# AltiumSTM32_Schematic.net
KiCad netlist of a schematic drawn in Altium Designer
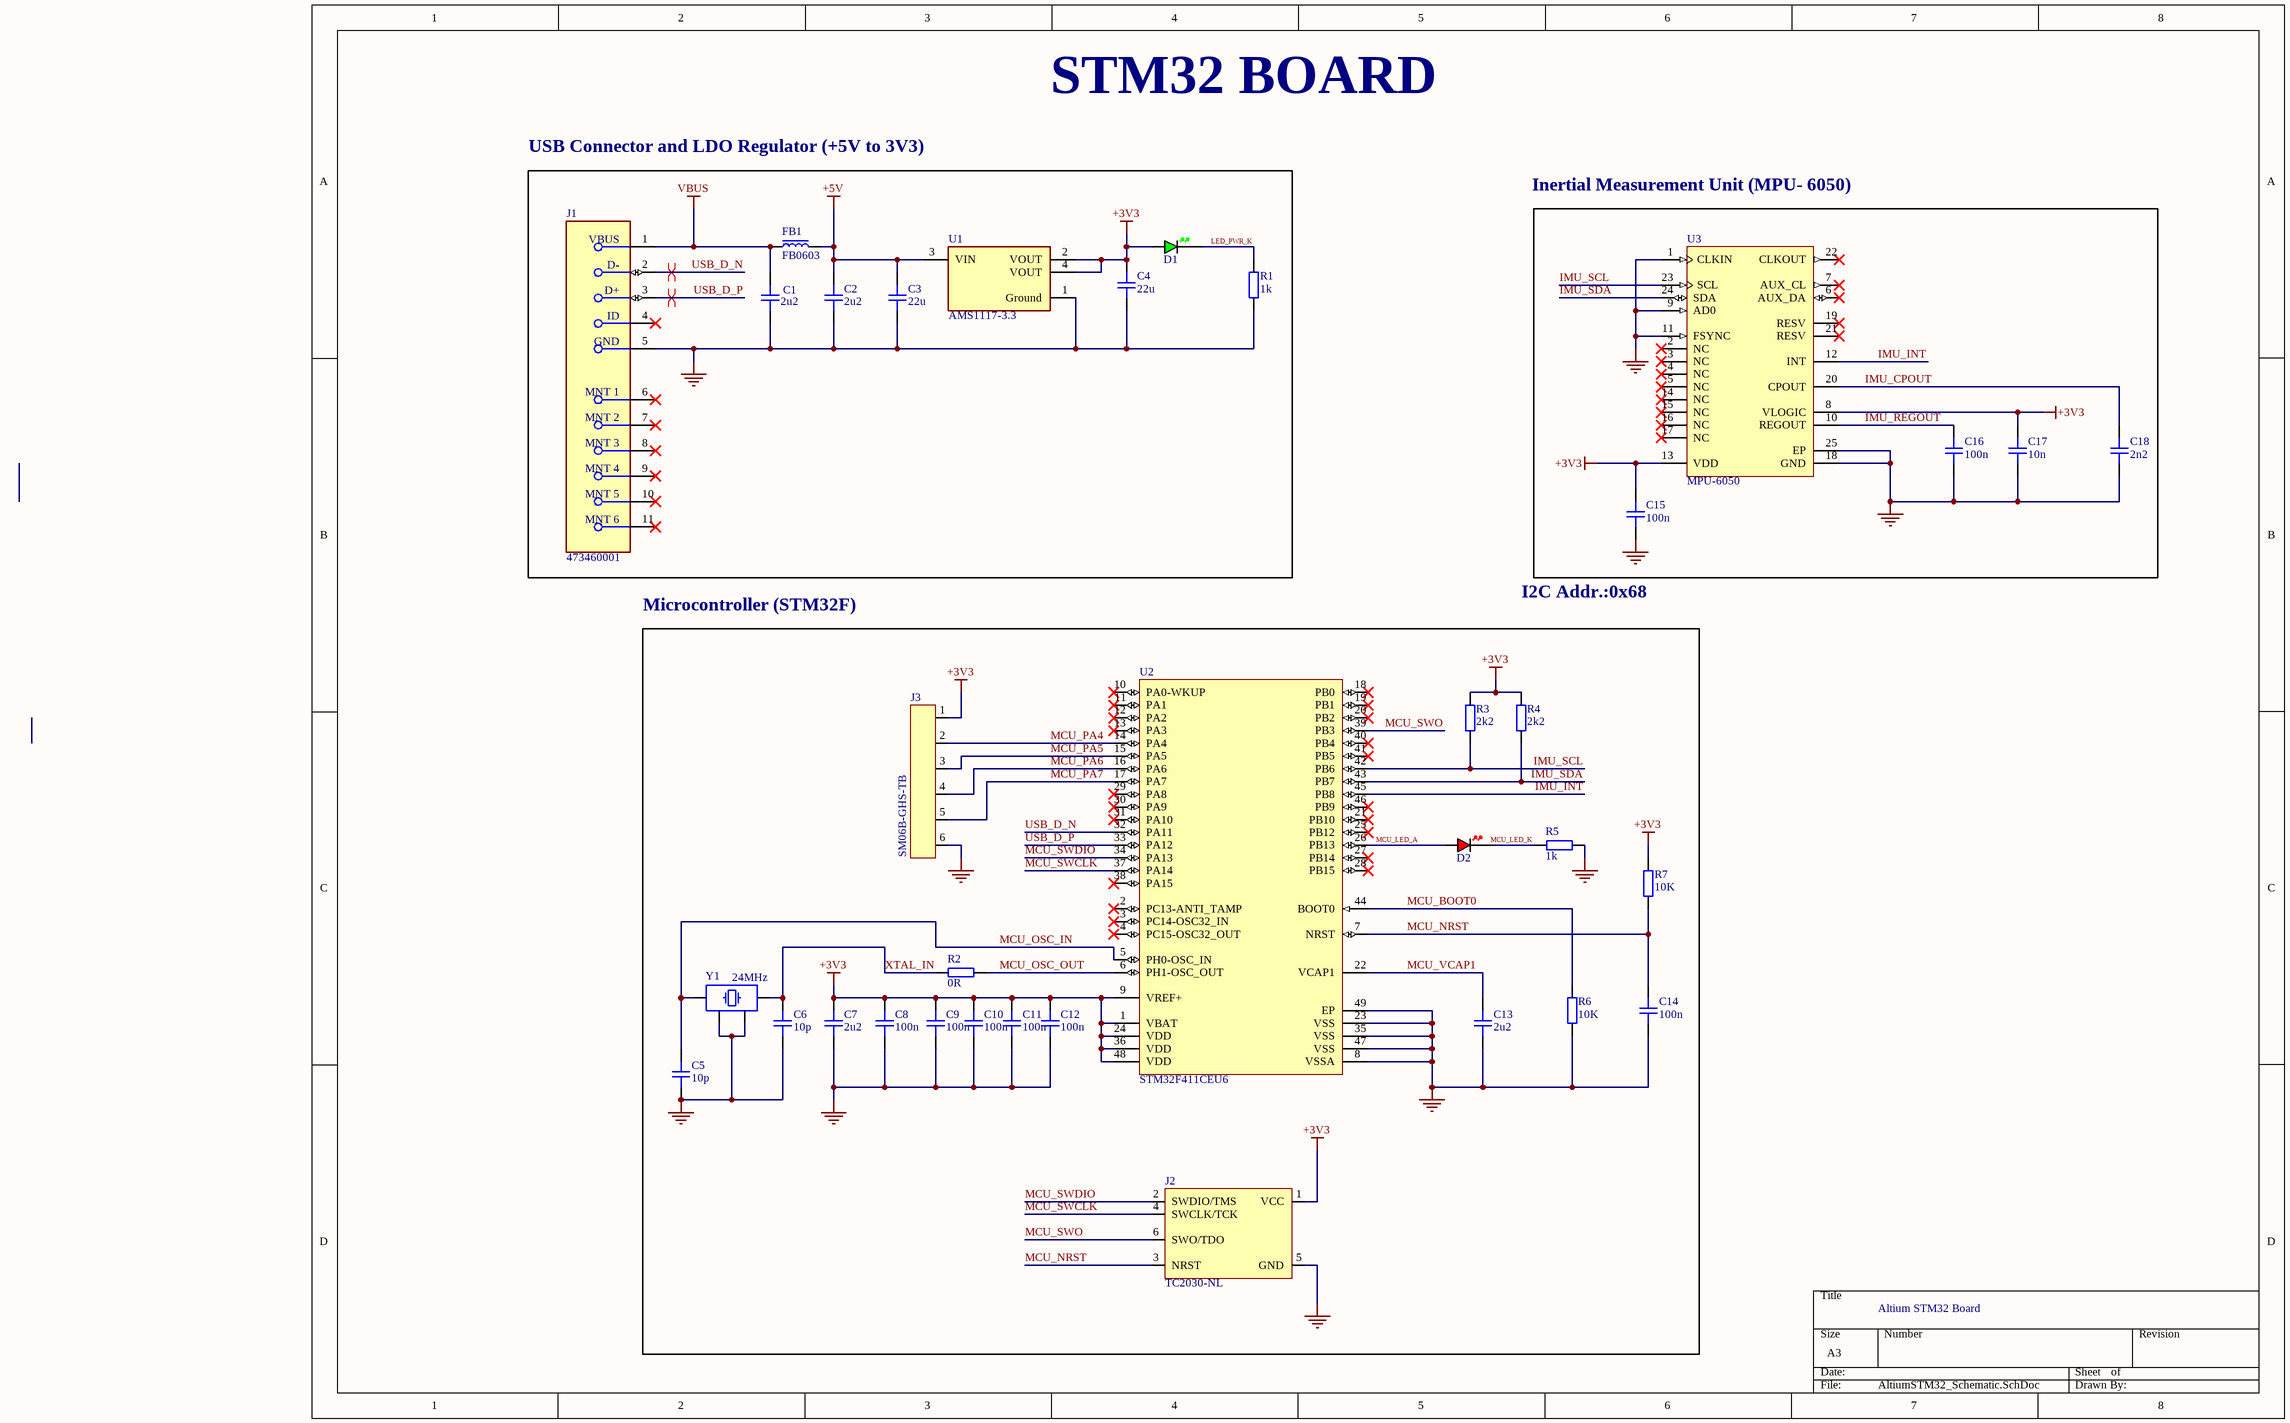
[diagram p0: AltiumSTM32_Schematic.SchDoc]

(export (version "E")
  (design (tool "Eeschema 10.0.6"))
  (components
    (comp (ref "C1")
      (value "2u2")
      (footprint "CAP_0603")
      (description "Capacitor SMD 0603 16V")
      (libsource (lib "Schematic-Lib-PhilsLab") (part "CAP_0603_16V"))
    )
    (comp (ref "C2")
      (value "2u2")
      (footprint "CAP_0603")
      (description "Capacitor SMD 0603 16V")
      (libsource (lib "Schematic-Lib-PhilsLab") (part "CAP_0603_16V"))
    )
    (comp (ref "C3")
      (value "22u")
      (footprint "CAP_0805")
      (description "Capacitor SMD 0805 16V")
      (libsource (lib "Schematic-Lib-PhilsLab") (part "CAP_0805_16V"))
    )
    (comp (ref "C4")
      (value "22u")
      (footprint "CAP_0805")
      (description "Capacitor SMD 0805 16V")
      (libsource (lib "Schematic-Lib-PhilsLab") (part "CAP_0805_16V"))
    )
    (comp (ref "C5")
      (value "10p")
      (footprint "CAP_0402")
      (description "Capacitor SMD 0402 16V")
      (libsource (lib "Schematic-Lib-PhilsLab") (part "CAP_0402_16V"))
    )
    (comp (ref "C6")
      (value "10p")
      (footprint "CAP_0402")
      (description "Capacitor SMD 0402 16V")
      (libsource (lib "Schematic-Lib-PhilsLab") (part "CAP_0402_16V"))
    )
    (comp (ref "C7")
      (value "2u2")
      (footprint "CAP_0603")
      (description "Capacitor SMD 0603 16V")
      (libsource (lib "Schematic-Lib-PhilsLab") (part "CAP_0603_16V"))
    )
    (comp (ref "C8")
      (value "100n")
      (footprint "CAP_0402")
      (description "Capacitor SMD 0402 16V")
      (libsource (lib "Schematic-Lib-PhilsLab") (part "CAP_0402_16V"))
    )
    (comp (ref "C9")
      (value "100n")
      (footprint "CAP_0402")
      (description "Capacitor SMD 0402 16V")
      (libsource (lib "Schematic-Lib-PhilsLab") (part "CAP_0402_16V"))
    )
    (comp (ref "C10")
      (value "100n")
      (footprint "CAP_0402")
      (description "Capacitor SMD 0402 16V")
      (libsource (lib "Schematic-Lib-PhilsLab") (part "CAP_0402_16V"))
    )
    (comp (ref "C11")
      (value "100n")
      (footprint "CAP_0402")
      (description "Capacitor SMD 0402 16V")
      (libsource (lib "Schematic-Lib-PhilsLab") (part "CAP_0402_16V"))
    )
    (comp (ref "C12")
      (value "100n")
      (footprint "CAP_0402")
      (description "Capacitor SMD 0402 16V")
      (libsource (lib "Schematic-Lib-PhilsLab") (part "CAP_0402_16V"))
    )
    (comp (ref "C13")
      (value "2u2")
      (footprint "CAP_0603")
      (description "Capacitor SMD 0603 16V")
      (libsource (lib "Schematic-Lib-PhilsLab") (part "CAP_0603_16V"))
    )
    (comp (ref "C14")
      (value "100n")
      (footprint "CAP_0402")
      (description "Capacitor SMD 0402 16V")
      (libsource (lib "Schematic-Lib-PhilsLab") (part "CAP_0402_16V"))
    )
    (comp (ref "C15")
      (value "100n")
      (footprint "CAP_0402")
      (description "Capacitor SMD 0402 16V")
      (libsource (lib "Schematic-Lib-PhilsLab") (part "CAP_0402_16V"))
    )
    (comp (ref "C16")
      (value "100n")
      (footprint "CAP_0402")
      (description "Capacitor SMD 0402 16V")
      (libsource (lib "Schematic-Lib-PhilsLab") (part "CAP_0402_16V"))
    )
    (comp (ref "C17")
      (value "10n")
      (footprint "CAP_0402")
      (description "Capacitor SMD 0402 16V")
      (libsource (lib "Schematic-Lib-PhilsLab") (part "CAP_0402_16V"))
    )
    (comp (ref "C18")
      (value "2n2")
      (footprint "CAP_0402")
      (description "Capacitor SMD 0402 16V")
      (libsource (lib "Schematic-Lib-PhilsLab") (part "CAP_0402_16V"))
    )
    (comp (ref "D1")
      (value "GREEN")
      (footprint "LED_0402_GREEN")
      (description "LED 0402 GREEN SMD")
      (libsource (lib "Schematic-Lib-PhilsLab") (part "LED_0402_GREEN"))
    )
    (comp (ref "D2")
      (value "RED")
      (footprint "LED_0402_RED")
      (description "LED 0402 RED SMD")
      (libsource (lib "Schematic-Lib-PhilsLab") (part "LED_0402_RED"))
    )
    (comp (ref "FB1")
      (value "FB0603")
      (footprint "FB_0603")
      (description "Ferrite Bead SMD 0603")
      (libsource (lib "Schematic-Lib-PhilsLab") (part "FB_0603"))
    )
    (comp (ref "J1")
      (value "473460001")
      (footprint "FP-473460001-MFG")
      (description "CONN RCPT USB2.0 MICRO B SMD R/A")
      (fields
        (field (name "OCTOPART") "https://octopart.com/47346-0001-molex-7164928")
        (field (name "MANUFACTURER") "Molex")
      )
      (libsource (lib "Altium Content Vault") (part "53ae1f1d9b557310b43ca686e5bb76a"))
    )
    (comp (ref "J2")
      (value "TC2030-NL")
      (footprint "TC2030-NL-FP")
      (description "Tag-Connect No-Solder SWD Debug Connector (No Legs) DO NOT PLACE")
      (fields
        (field (name "MANUFACTURER") "Tag-Connect")
        (field (name "MANUFACTURER PART NUMBER") "TC2030-NL-FP")
      )
      (libsource (lib "Schematic-Lib-PhilsLab") (part "TC2030-NL"))
    )
    (comp (ref "J3")
      (value "SM06B-GHS-TB")
      (footprint "SM06B-GHS-TB")
      (description "Header Connector 6 Position 1.25MM Pitch SMD Horizontal JST GH")
      (fields (field (name "MANUFACTURER") "JST"))
      (libsource (lib "Schematic-Lib-PhilsLab") (part "SM06B-GHS-TB"))
    )
    (comp (ref "R1")
      (value "1k")
      (footprint "RES_0402")
      (description "Resistor SMD 0402")
      (libsource (lib "Schematic-Lib-PhilsLab") (part "RES_0402"))
    )
    (comp (ref "R2")
      (value "0R")
      (footprint "RES_0402")
      (description "Resistor SMD 0402")
      (libsource (lib "Schematic-Lib-PhilsLab") (part "RES_0402"))
    )
    (comp (ref "R3")
      (value "2k2")
      (footprint "RES_0402")
      (description "Resistor SMD 0402")
      (libsource (lib "Schematic-Lib-PhilsLab") (part "RES_0402"))
    )
    (comp (ref "R4")
      (value "2k2")
      (footprint "RES_0402")
      (description "Resistor SMD 0402")
      (libsource (lib "Schematic-Lib-PhilsLab") (part "RES_0402"))
    )
    (comp (ref "R5")
      (value "1k")
      (footprint "RES_0402")
      (description "Resistor SMD 0402")
      (libsource (lib "Schematic-Lib-PhilsLab") (part "RES_0402"))
    )
    (comp (ref "R6")
      (value "10K")
      (footprint "RES_0402")
      (description "Resistor SMD 0402")
      (libsource (lib "Schematic-Lib-PhilsLab") (part "RES_0402"))
    )
    (comp (ref "R7")
      (value "10K")
      (footprint "RES_0402")
      (description "Resistor SMD 0402")
      (libsource (lib "Schematic-Lib-PhilsLab") (part "RES_0402"))
    )
    (comp (ref "U1")
      (value "AMS1117-3.3")
      (footprint "FP-AMS1117-IPC_C")
      (description "LDO Voltage Regulators 1A, 3.3V")
      (fields
        (field (name "OCTOPART") "https://octopart.com/ams1117-3.3-advanced+monolithic+systems-25899300")
        (field (name "MANUFACTURER") "Advanced Monolithic Systems")
      )
      (libsource (lib "Altium Content Vault") (part "8bdbb5f8e77002000e30dd2845d0354"))
    )
    (comp (ref "U2")
      (value "STM32F411CEU6")
      (footprint "STM-UFQFPN48_L")
      (libsource (lib "Altium Content Vault") (part "MC-ARM-STM32F411-UFQFPN48"))
    )
    (comp (ref "U3")
      (value "MPU-6050")
      (footprint "IS-QFN-24_V")
      (fields (field (name "MANUFACTURER") "InvenSense"))
      (libsource (lib "Altium Content Vault") (part "IS-MPU-6050-QFN-24"))
    )
    (comp (ref "Y1")
      (value "24MHz")
      (footprint "XTAL_3225")
      (description "Crystal SMD 24MHz 10PPM 7pF 3225")
      (fields (field (name "MANUFACTURER") "Epson"))
      (libsource (lib "Schematic-Lib-PhilsLab") (part "TSX-3225_24.0000MF15X-AC"))
    )
  )
  (nets
    (net (code "1") (name "+3V3") (class "Default")
      (node (ref "C10") (pin "2") (pinfunction "2_2") (pintype "passive"))
      (node (ref "C11") (pin "2") (pinfunction "2_2") (pintype "passive"))
      (node (ref "C12") (pin "2") (pinfunction "2_2") (pintype "passive"))
      (node (ref "C15") (pin "2") (pinfunction "2_2") (pintype "passive"))
      (node (ref "C17") (pin "2") (pinfunction "2_2") (pintype "passive"))
      (node (ref "C4") (pin "2") (pinfunction "2_2") (pintype "passive"))
      (node (ref "C7") (pin "2") (pinfunction "2_2") (pintype "passive"))
      (node (ref "C8") (pin "2") (pinfunction "2_2") (pintype "passive"))
      (node (ref "C9") (pin "2") (pinfunction "2_2") (pintype "passive"))
      (node (ref "D1") (pin "A") (pinfunction "A_A") (pintype "passive"))
      (node (ref "J2") (pin "1") (pinfunction "VCC_1") (pintype "passive"))
      (node (ref "J3") (pin "1") (pinfunction "1_1") (pintype "passive"))
      (node (ref "R3") (pin "2") (pinfunction "2_2") (pintype "passive"))
      (node (ref "R4") (pin "2") (pinfunction "2_2") (pintype "passive"))
      (node (ref "R7") (pin "1") (pinfunction "1_1") (pintype "passive"))
      (node (ref "U1") (pin "2") (pinfunction "VOUT_2") (pintype "passive"))
      (node (ref "U1") (pin "4") (pinfunction "VOUT_4") (pintype "passive"))
      (node (ref "U2") (pin "1") (pinfunction "VBAT_1") (pintype "power_in"))
      (node (ref "U2") (pin "24") (pinfunction "VDD_24") (pintype "power_in"))
      (node (ref "U2") (pin "36") (pinfunction "VDD_36") (pintype "power_in"))
      (node (ref "U2") (pin "48") (pinfunction "VDD_48") (pintype "power_in"))
      (node (ref "U2") (pin "9") (pinfunction "VREF+_9") (pintype "power_in"))
      (node (ref "U3") (pin "13") (pinfunction "VDD_13") (pintype "power_in"))
      (node (ref "U3") (pin "8") (pinfunction "VLOGIC_8") (pintype "power_in"))
    )
    (net (code "2") (name "+5V") (class "Default")
      (node (ref "C2") (pin "2") (pinfunction "2_2") (pintype "passive"))
      (node (ref "C3") (pin "2") (pinfunction "2_2") (pintype "passive"))
      (node (ref "FB1") (pin "2") (pinfunction "2_2") (pintype "passive"))
      (node (ref "U1") (pin "3") (pinfunction "VIN_3") (pintype "power_in"))
    )
    (net (code "3") (name "/IMU_CPOUT") (class "Default")
      (node (ref "C18") (pin "2") (pinfunction "2_2") (pintype "passive"))
      (node (ref "U3") (pin "20") (pinfunction "CPOUT_20") (pintype "passive"))
    )
    (net (code "4") (name "/IMU_INT") (class "Default")
      (node (ref "U2") (pin "45") (pinfunction "PB8_45") (pintype "bidirectional"))
      (node (ref "U3") (pin "12") (pinfunction "INT_12") (pintype "open_collector"))
    )
    (net (code "5") (name "/IMU_REGOUT") (class "Default")
      (node (ref "C16") (pin "2") (pinfunction "2_2") (pintype "passive"))
      (node (ref "U3") (pin "10") (pinfunction "REGOUT_10") (pintype "passive"))
    )
    (net (code "6") (name "/IMU_SCL") (class "Default")
      (node (ref "R3") (pin "1") (pinfunction "1_1") (pintype "passive"))
      (node (ref "U2") (pin "42") (pinfunction "PB6_42") (pintype "bidirectional"))
      (node (ref "U3") (pin "23") (pinfunction "SCL_23") (pintype "input"))
    )
    (net (code "7") (name "/IMU_SDA") (class "Default")
      (node (ref "R4") (pin "1") (pinfunction "1_1") (pintype "passive"))
      (node (ref "U2") (pin "43") (pinfunction "PB7_43") (pintype "bidirectional"))
      (node (ref "U3") (pin "24") (pinfunction "SDA_24") (pintype "bidirectional"))
    )
    (net (code "8") (name "/LED_PWR_K") (class "Default")
      (node (ref "D1") (pin "K") (pinfunction "K_K") (pintype "passive"))
      (node (ref "R1") (pin "2") (pinfunction "2_2") (pintype "passive"))
    )
    (net (code "9") (name "/MCU_BOOT0") (class "Default")
      (node (ref "R6") (pin "1") (pinfunction "1_1") (pintype "passive"))
      (node (ref "U2") (pin "44") (pinfunction "BOOT0_44") (pintype "input"))
    )
    (net (code "10") (name "/MCU_LED_A") (class "Default")
      (node (ref "D2") (pin "A") (pinfunction "A_A") (pintype "passive"))
      (node (ref "U2") (pin "26") (pinfunction "PB13_26") (pintype "bidirectional"))
    )
    (net (code "11") (name "/MCU_LED_K") (class "Default")
      (node (ref "D2") (pin "K") (pinfunction "K_K") (pintype "passive"))
      (node (ref "R5") (pin "1") (pinfunction "1_1") (pintype "passive"))
    )
    (net (code "12") (name "/MCU_NRST") (class "Default")
      (node (ref "C14") (pin "2") (pinfunction "2_2") (pintype "passive"))
      (node (ref "J2") (pin "3") (pinfunction "NRST_3") (pintype "passive"))
      (node (ref "R7") (pin "2") (pinfunction "2_2") (pintype "passive"))
      (node (ref "U2") (pin "7") (pinfunction "NRST_7") (pintype "bidirectional"))
    )
    (net (code "13") (name "/MCU_OSC_IN") (class "Default")
      (node (ref "C5") (pin "2") (pinfunction "2_2") (pintype "passive"))
      (node (ref "U2") (pin "5") (pinfunction "PH0-OSC_IN_5") (pintype "bidirectional"))
      (node (ref "Y1") (pin "1") (pinfunction "1_1") (pintype "passive"))
    )
    (net (code "14") (name "/MCU_OSC_OUT") (class "Default")
      (node (ref "R2") (pin "2") (pinfunction "2_2") (pintype "passive"))
      (node (ref "U2") (pin "6") (pinfunction "PH1-OSC_OUT_6") (pintype "bidirectional"))
    )
    (net (code "15") (name "/MCU_PA4") (class "Default")
      (node (ref "J3") (pin "2") (pinfunction "2_2") (pintype "passive"))
      (node (ref "U2") (pin "14") (pinfunction "PA4_14") (pintype "bidirectional"))
    )
    (net (code "16") (name "/MCU_PA5") (class "Default")
      (node (ref "J3") (pin "3") (pinfunction "3_3") (pintype "passive"))
      (node (ref "U2") (pin "15") (pinfunction "PA5_15") (pintype "bidirectional"))
    )
    (net (code "17") (name "/MCU_PA6") (class "Default")
      (node (ref "J3") (pin "4") (pinfunction "4_4") (pintype "passive"))
      (node (ref "U2") (pin "16") (pinfunction "PA6_16") (pintype "bidirectional"))
    )
    (net (code "18") (name "/MCU_PA7") (class "Default")
      (node (ref "J3") (pin "5") (pinfunction "5_5") (pintype "passive"))
      (node (ref "U2") (pin "17") (pinfunction "PA7_17") (pintype "bidirectional"))
    )
    (net (code "19") (name "/MCU_SWCLK") (class "Default")
      (node (ref "J2") (pin "4") (pinfunction "SWCLK/TCK_4") (pintype "passive"))
      (node (ref "U2") (pin "37") (pinfunction "PA14_37") (pintype "bidirectional"))
    )
    (net (code "20") (name "/MCU_SWDIO") (class "Default")
      (node (ref "J2") (pin "2") (pinfunction "SWDIO/TMS_2") (pintype "passive"))
      (node (ref "U2") (pin "34") (pinfunction "PA13_34") (pintype "bidirectional"))
    )
    (net (code "21") (name "/MCU_SWO") (class "Default")
      (node (ref "J2") (pin "6") (pinfunction "SWO/TDO_6") (pintype "passive"))
      (node (ref "U2") (pin "39") (pinfunction "PB3_39") (pintype "bidirectional"))
    )
    (net (code "22") (name "/MCU_VCAP1") (class "Default")
      (node (ref "C13") (pin "2") (pinfunction "2_2") (pintype "passive"))
      (node (ref "U2") (pin "22") (pinfunction "VCAP1_22") (pintype "passive"))
    )
    (net (code "23") (name "/USB_D_N") (class "Default")
      (node (ref "J1") (pin "2") (pinfunction "D-_2") (pintype "bidirectional"))
      (node (ref "U2") (pin "32") (pinfunction "PA11_32") (pintype "bidirectional"))
    )
    (net (code "24") (name "/USB_D_P") (class "Default")
      (node (ref "J1") (pin "3") (pinfunction "D+_3") (pintype "bidirectional"))
      (node (ref "U2") (pin "33") (pinfunction "PA12_33") (pintype "bidirectional"))
    )
    (net (code "25") (name "/XTAL_IN") (class "Default")
      (node (ref "C6") (pin "2") (pinfunction "2_2") (pintype "passive"))
      (node (ref "R2") (pin "1") (pinfunction "1_1") (pintype "passive"))
      (node (ref "Y1") (pin "3") (pinfunction "3_3") (pintype "passive"))
    )
    (net (code "26") (name "GND") (class "Default")
      (node (ref "C1") (pin "1") (pinfunction "1_1") (pintype "passive"))
      (node (ref "C10") (pin "1") (pinfunction "1_1") (pintype "passive"))
      (node (ref "C11") (pin "1") (pinfunction "1_1") (pintype "passive"))
      (node (ref "C12") (pin "1") (pinfunction "1_1") (pintype "passive"))
      (node (ref "C13") (pin "1") (pinfunction "1_1") (pintype "passive"))
      (node (ref "C14") (pin "1") (pinfunction "1_1") (pintype "passive"))
      (node (ref "C15") (pin "1") (pinfunction "1_1") (pintype "passive"))
      (node (ref "C16") (pin "1") (pinfunction "1_1") (pintype "passive"))
      (node (ref "C17") (pin "1") (pinfunction "1_1") (pintype "passive"))
      (node (ref "C18") (pin "1") (pinfunction "1_1") (pintype "passive"))
      (node (ref "C2") (pin "1") (pinfunction "1_1") (pintype "passive"))
      (node (ref "C3") (pin "1") (pinfunction "1_1") (pintype "passive"))
      (node (ref "C4") (pin "1") (pinfunction "1_1") (pintype "passive"))
      (node (ref "C5") (pin "1") (pinfunction "1_1") (pintype "passive"))
      (node (ref "C6") (pin "1") (pinfunction "1_1") (pintype "passive"))
      (node (ref "C7") (pin "1") (pinfunction "1_1") (pintype "passive"))
      (node (ref "C8") (pin "1") (pinfunction "1_1") (pintype "passive"))
      (node (ref "C9") (pin "1") (pinfunction "1_1") (pintype "passive"))
      (node (ref "J1") (pin "5") (pinfunction "GND_5") (pintype "power_in"))
      (node (ref "J2") (pin "5") (pinfunction "GND_5") (pintype "passive"))
      (node (ref "J3") (pin "6") (pinfunction "6_6") (pintype "passive"))
      (node (ref "R1") (pin "1") (pinfunction "1_1") (pintype "passive"))
      (node (ref "R5") (pin "2") (pinfunction "2_2") (pintype "passive"))
      (node (ref "R6") (pin "2") (pinfunction "2_2") (pintype "passive"))
      (node (ref "U1") (pin "1") (pinfunction "Ground_1") (pintype "power_in"))
      (node (ref "U2") (pin "23") (pinfunction "VSS_23") (pintype "power_in"))
      (node (ref "U2") (pin "35") (pinfunction "VSS_35") (pintype "power_in"))
      (node (ref "U2") (pin "47") (pinfunction "VSS_47") (pintype "power_in"))
      (node (ref "U2") (pin "49") (pinfunction "EP_49") (pintype "power_in"))
      (node (ref "U2") (pin "8") (pinfunction "VSSA_8") (pintype "power_in"))
      (node (ref "U3") (pin "1") (pinfunction "CLKIN_1") (pintype "input"))
      (node (ref "U3") (pin "11") (pinfunction "FSYNC_11") (pintype "input"))
      (node (ref "U3") (pin "18") (pinfunction "GND_18") (pintype "power_in"))
      (node (ref "U3") (pin "25") (pinfunction "EP_25") (pintype "power_in"))
      (node (ref "U3") (pin "9") (pinfunction "AD0_9") (pintype "input"))
      (node (ref "Y1") (pin "2") (pinfunction "2_2") (pintype "passive"))
      (node (ref "Y1") (pin "4") (pinfunction "4_4") (pintype "passive"))
    )
    (net (code "27") (name "VBUS") (class "Default")
      (node (ref "C1") (pin "2") (pinfunction "2_2") (pintype "passive"))
      (node (ref "FB1") (pin "1") (pinfunction "1_1") (pintype "passive"))
      (node (ref "J1") (pin "1") (pinfunction "VBUS_1") (pintype "power_in"))
    )
    (net (code "28") (name "unconnected-(J1-ID-Pad4)") (class "Default")
      (node (ref "J1") (pin "4") (pinfunction "ID_4") (pintype "passive+no_connect"))
    )
    (net (code "29") (name "unconnected-(J1-MNT_1-Pad6)") (class "Default")
      (node (ref "J1") (pin "6") (pinfunction "MNT_1_6") (pintype "passive+no_connect"))
    )
    (net (code "30") (name "unconnected-(J1-MNT_2-Pad7)") (class "Default")
      (node (ref "J1") (pin "7") (pinfunction "MNT_2_7") (pintype "passive+no_connect"))
    )
    (net (code "31") (name "unconnected-(J1-MNT_3-Pad8)") (class "Default")
      (node (ref "J1") (pin "8") (pinfunction "MNT_3_8") (pintype "passive+no_connect"))
    )
    (net (code "32") (name "unconnected-(J1-MNT_4-Pad9)") (class "Default")
      (node (ref "J1") (pin "9") (pinfunction "MNT_4_9") (pintype "passive+no_connect"))
    )
    (net (code "33") (name "unconnected-(J1-MNT_5-Pad10)") (class "Default")
      (node (ref "J1") (pin "10") (pinfunction "MNT_5_10") (pintype "passive+no_connect"))
    )
    (net (code "34") (name "unconnected-(J1-MNT_6-Pad11)") (class "Default")
      (node (ref "J1") (pin "11") (pinfunction "MNT_6_11") (pintype "passive+no_connect"))
    )
    (net (code "35") (name "unconnected-(U2-PA0-WKUP-Pad10)") (class "Default")
      (node (ref "U2") (pin "10") (pinfunction "PA0-WKUP_10") (pintype "bidirectional+no_connect"))
    )
    (net (code "36") (name "unconnected-(U2-PA1-Pad11)") (class "Default")
      (node (ref "U2") (pin "11") (pinfunction "PA1_11") (pintype "bidirectional+no_connect"))
    )
    (net (code "37") (name "unconnected-(U2-PA2-Pad12)") (class "Default")
      (node (ref "U2") (pin "12") (pinfunction "PA2_12") (pintype "bidirectional+no_connect"))
    )
    (net (code "38") (name "unconnected-(U2-PA3-Pad13)") (class "Default")
      (node (ref "U2") (pin "13") (pinfunction "PA3_13") (pintype "bidirectional+no_connect"))
    )
    (net (code "39") (name "unconnected-(U2-PA8-Pad29)") (class "Default")
      (node (ref "U2") (pin "29") (pinfunction "PA8_29") (pintype "bidirectional+no_connect"))
    )
    (net (code "40") (name "unconnected-(U2-PA9-Pad30)") (class "Default")
      (node (ref "U2") (pin "30") (pinfunction "PA9_30") (pintype "bidirectional+no_connect"))
    )
    (net (code "41") (name "unconnected-(U2-PA10-Pad31)") (class "Default")
      (node (ref "U2") (pin "31") (pinfunction "PA10_31") (pintype "bidirectional+no_connect"))
    )
    (net (code "42") (name "unconnected-(U2-PA15-Pad38)") (class "Default")
      (node (ref "U2") (pin "38") (pinfunction "PA15_38") (pintype "bidirectional+no_connect"))
    )
    (net (code "43") (name "unconnected-(U2-PB0-Pad18)") (class "Default")
      (node (ref "U2") (pin "18") (pinfunction "PB0_18") (pintype "bidirectional+no_connect"))
    )
    (net (code "44") (name "unconnected-(U2-PB1-Pad19)") (class "Default")
      (node (ref "U2") (pin "19") (pinfunction "PB1_19") (pintype "bidirectional+no_connect"))
    )
    (net (code "45") (name "unconnected-(U2-PB2-Pad20)") (class "Default")
      (node (ref "U2") (pin "20") (pinfunction "PB2_20") (pintype "bidirectional+no_connect"))
    )
    (net (code "46") (name "unconnected-(U2-PB4-Pad40)") (class "Default")
      (node (ref "U2") (pin "40") (pinfunction "PB4_40") (pintype "bidirectional+no_connect"))
    )
    (net (code "47") (name "unconnected-(U2-PB5-Pad41)") (class "Default")
      (node (ref "U2") (pin "41") (pinfunction "PB5_41") (pintype "bidirectional+no_connect"))
    )
    (net (code "48") (name "unconnected-(U2-PB9-Pad46)") (class "Default")
      (node (ref "U2") (pin "46") (pinfunction "PB9_46") (pintype "bidirectional+no_connect"))
    )
    (net (code "49") (name "unconnected-(U2-PB10-Pad21)") (class "Default")
      (node (ref "U2") (pin "21") (pinfunction "PB10_21") (pintype "bidirectional+no_connect"))
    )
    (net (code "50") (name "unconnected-(U2-PB12-Pad25)") (class "Default")
      (node (ref "U2") (pin "25") (pinfunction "PB12_25") (pintype "bidirectional+no_connect"))
    )
    (net (code "51") (name "unconnected-(U2-PB14-Pad27)") (class "Default")
      (node (ref "U2") (pin "27") (pinfunction "PB14_27") (pintype "bidirectional+no_connect"))
    )
    (net (code "52") (name "unconnected-(U2-PB15-Pad28)") (class "Default")
      (node (ref "U2") (pin "28") (pinfunction "PB15_28") (pintype "bidirectional+no_connect"))
    )
    (net (code "53") (name "unconnected-(U2-PC13-ANTI_TAMP-Pad2)") (class "Default")
      (node (ref "U2") (pin "2") (pinfunction "PC13-ANTI_TAMP_2") (pintype "bidirectional+no_connect"))
    )
    (net (code "54") (name "unconnected-(U2-PC14-OSC32_IN-Pad3)") (class "Default")
      (node (ref "U2") (pin "3") (pinfunction "PC14-OSC32_IN_3") (pintype "bidirectional+no_connect"))
    )
    (net (code "55") (name "unconnected-(U2-PC15-OSC32_OUT-Pad4)") (class "Default")
      (node (ref "U2") (pin "4") (pinfunction "PC15-OSC32_OUT_4") (pintype "bidirectional+no_connect"))
    )
    (net (code "56") (name "unconnected-(U3-AUX_CL-Pad7)") (class "Default")
      (node (ref "U3") (pin "7") (pinfunction "AUX_CL_7") (pintype "output+no_connect"))
    )
    (net (code "57") (name "unconnected-(U3-AUX_DA-Pad6)") (class "Default")
      (node (ref "U3") (pin "6") (pinfunction "AUX_DA_6") (pintype "bidirectional+no_connect"))
    )
    (net (code "58") (name "unconnected-(U3-CLKOUT-Pad22)") (class "Default")
      (node (ref "U3") (pin "22") (pinfunction "CLKOUT_22") (pintype "output+no_connect"))
    )
    (net (code "59") (name "unconnected-(U3-NC-Pad2)") (class "Default")
      (node (ref "U3") (pin "2") (pinfunction "NC_2") (pintype "passive+no_connect"))
    )
    (net (code "60") (name "unconnected-(U3-NC-Pad3)") (class "Default")
      (node (ref "U3") (pin "3") (pinfunction "NC_3") (pintype "passive+no_connect"))
    )
    (net (code "61") (name "unconnected-(U3-NC-Pad4)") (class "Default")
      (node (ref "U3") (pin "4") (pinfunction "NC_4") (pintype "passive+no_connect"))
    )
    (net (code "62") (name "unconnected-(U3-NC-Pad5)") (class "Default")
      (node (ref "U3") (pin "5") (pinfunction "NC_5") (pintype "passive+no_connect"))
    )
    (net (code "63") (name "unconnected-(U3-NC-Pad14)") (class "Default")
      (node (ref "U3") (pin "14") (pinfunction "NC_14") (pintype "passive+no_connect"))
    )
    (net (code "64") (name "unconnected-(U3-NC-Pad15)") (class "Default")
      (node (ref "U3") (pin "15") (pinfunction "NC_15") (pintype "passive+no_connect"))
    )
    (net (code "65") (name "unconnected-(U3-NC-Pad16)") (class "Default")
      (node (ref "U3") (pin "16") (pinfunction "NC_16") (pintype "passive+no_connect"))
    )
    (net (code "66") (name "unconnected-(U3-NC-Pad17)") (class "Default")
      (node (ref "U3") (pin "17") (pinfunction "NC_17") (pintype "passive+no_connect"))
    )
    (net (code "67") (name "unconnected-(U3-RESV-Pad19)") (class "Default")
      (node (ref "U3") (pin "19") (pinfunction "RESV_19") (pintype "passive+no_connect"))
    )
    (net (code "68") (name "unconnected-(U3-RESV-Pad21)") (class "Default")
      (node (ref "U3") (pin "21") (pinfunction "RESV_21") (pintype "passive+no_connect"))
    )
  )
)
